# MinieasySens-RFM_V03-Build001.net
KiCad netlist of a schematic drawn in EAGLE
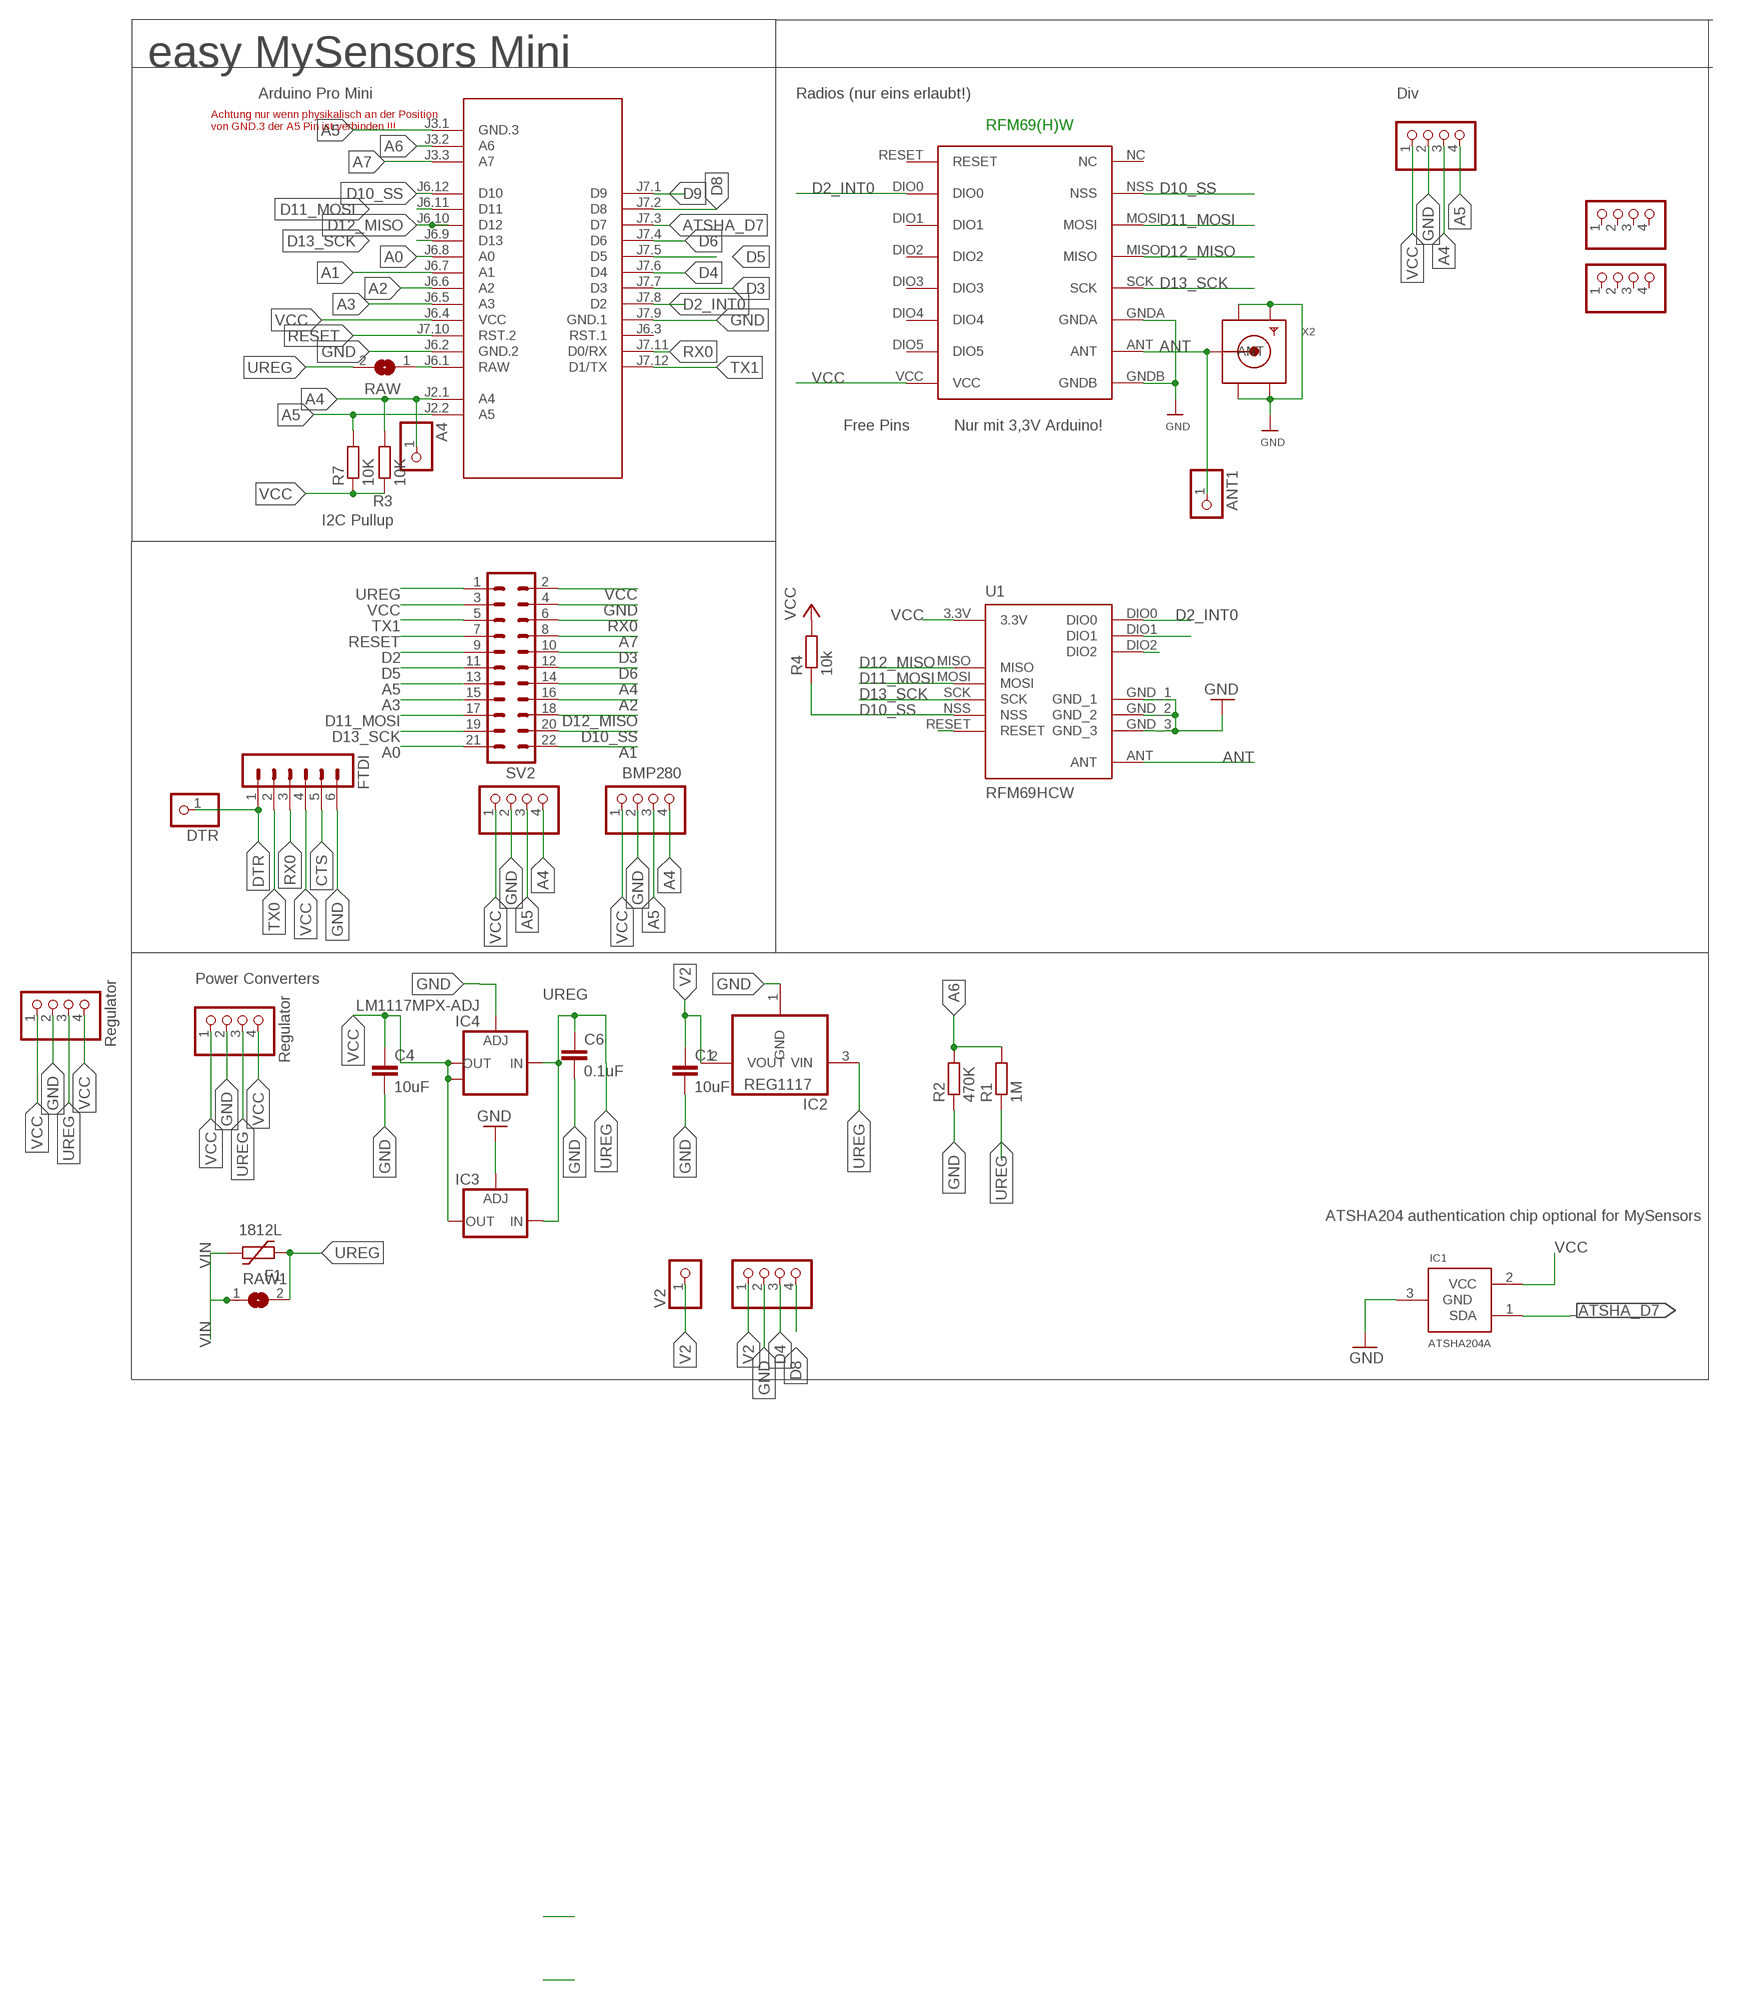
[diagram p0: schematic, sheet 1, part 1 of 2]
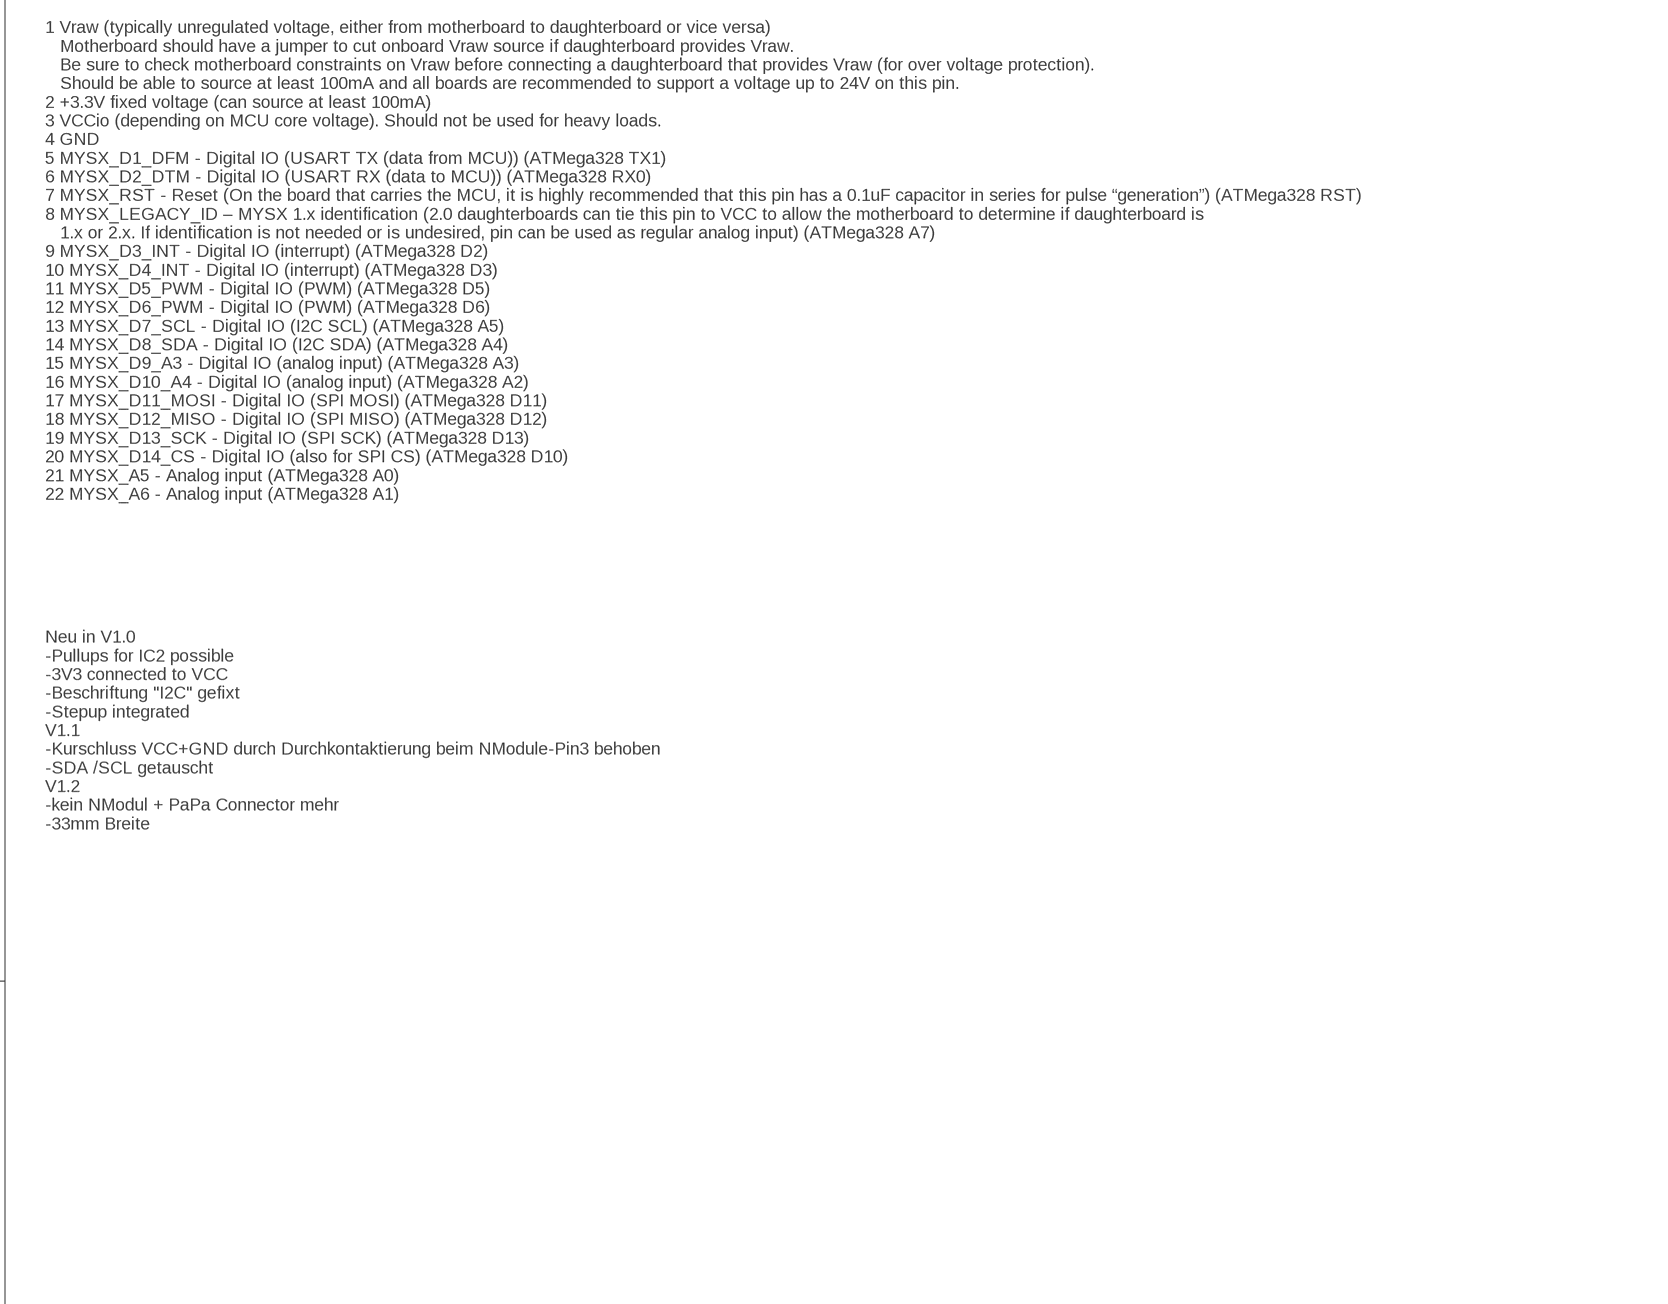
[diagram p1: schematic, sheet 1, part 2 of 2]

(export (version "E")
  (design (tool "Eeschema 10.0.6"))
  (components
    (comp (ref "A4")
      (value "PINHD-1X1")
      (footprint "eagle-import:1X01")
      (libsource (lib "eagle-import") (part "PINHD-1X1"))
    )
    (comp (ref "ANT1")
      (value "PINHD-1X1")
      (footprint "eagle-import:1X01")
      (libsource (lib "eagle-import") (part "PINHD-1X1"))
    )
    (comp (ref "BH1750")
      (value "PINHD-1X04_2.54-S")
      (footprint "eagle-import:1X04-S")
      (libsource (lib "eagle-import") (part "PINHD-1X04_2.54-S"))
    )
    (comp (ref "C1")
      (value "10uF")
      (footprint "eagle-import:C1210")
      (libsource (lib "eagle-import") (part "C-EUC1210"))
    )
    (comp (ref "C4")
      (value "10uF")
      (footprint "eagle-import:C1210")
      (libsource (lib "eagle-import") (part "C-EUC1210"))
    )
    (comp (ref "C6")
      (value "0.1uF")
      (footprint "eagle-import:C1206")
      (libsource (lib "eagle-import") (part "C-EUC1206"))
    )
    (comp (ref "DTR")
      (value "PINHD-1X1")
      (footprint "eagle-import:1X01")
      (libsource (lib "eagle-import") (part "PINHD-1X1"))
    )
    (comp (ref "F1")
      (value "1812L")
      (footprint "eagle-import:1812L")
      (libsource (lib "eagle-import") (part "1812L"))
    )
    (comp (ref "FTDI")
      (value "MA06-1")
      (footprint "eagle-import:MA06-1")
      (libsource (lib "eagle-import") (part "MA06-1"))
    )
    (comp (ref "I2C-1")
      (value "PINHD-1X04_2.54-S")
      (footprint "eagle-import:1X04-S")
      (libsource (lib "eagle-import") (part "PINHD-1X04_2.54-S"))
    )
    (comp (ref "I2C-2")
      (value "PINHD-1X04_2.54-S")
      (footprint "eagle-import:1X04-S")
      (libsource (lib "eagle-import") (part "PINHD-1X04_2.54-S"))
    )
    (comp (ref "IC1")
      (value "ATSHA204A")
      (footprint "eagle-import:SOT23")
      (libsource (lib "eagle-import") (part "ATSHA204A"))
    )
    (comp (ref "IC2")
      (value "REG1117")
      (footprint "eagle-import:SOT223")
      (libsource (lib "eagle-import") (part "REG1117"))
    )
    (comp (ref "IC3")
      (value "LD117ADT50TR")
      (footprint "eagle-import:DPACK")
      (libsource (lib "eagle-import") (part "LD117A?DT50TR"))
    )
    (comp (ref "IC4")
      (value "LM1117MPX-ADJ")
      (footprint "eagle-import:SOT223")
      (libsource (lib "eagle-import") (part "LM1117MPX-ADJ"))
    )
    (comp (ref "JP1")
      (value "PINHD-1X04_2.54-S")
      (footprint "eagle-import:1X04-S")
      (libsource (lib "eagle-import") (part "PINHD-1X04_2.54-S"))
    )
    (comp (ref "JP2")
      (value "PINHD-1X04_2.54-S")
      (footprint "eagle-import:1X04-S")
      (libsource (lib "eagle-import") (part "PINHD-1X04_2.54-S"))
    )
    (comp (ref "M1")
      (value "ARDUINO-PRO-MINI-3.3V#NP")
      (footprint "eagle-import:ARDUINO-PRO-MINI#NP")
      (libsource (lib "eagle-import") (part "ARDUINO-PRO-MINI-#NP3.3V"))
    )
    (comp (ref "R1")
      (value "1M")
      (footprint "eagle-import:R0805")
      (libsource (lib "eagle-import") (part "R-EU_R0805"))
    )
    (comp (ref "R2")
      (value "470K")
      (footprint "eagle-import:R0805")
      (libsource (lib "eagle-import") (part "R-EU_R0805"))
    )
    (comp (ref "R3")
      (value "10K")
      (footprint "eagle-import:R0805")
      (libsource (lib "eagle-import") (part "R-EU_R0805"))
    )
    (comp (ref "R4")
      (value "10k")
      (footprint "eagle-import:M0805")
      (libsource (lib "eagle-import") (part "R-EU_M0805"))
    )
    (comp (ref "R7")
      (value "10K")
      (footprint "eagle-import:R0805")
      (libsource (lib "eagle-import") (part "R-EU_R0805"))
    )
    (comp (ref "RAW") (value "SJ") (footprint "eagle-import:SJ") (libsource (lib "eagle-import") (part "SJ")))
    (comp (ref "RAW1")
      (value "SJ")
      (footprint "eagle-import:SJ")
      (libsource (lib "eagle-import") (part "SJ"))
    )
    (comp (ref "RFM69W")
      (value "RFM69HW")
      (footprint "eagle-import:RFM")
      (libsource (lib "eagle-import") (part "RFM69HW"))
    )
    (comp (ref "STEPDWN")
      (value "PINHD-1X04_2.54-S")
      (footprint "eagle-import:1X04-S")
      (libsource (lib "eagle-import") (part "PINHD-1X04_2.54-S"))
    )
    (comp (ref "STEPDWN1")
      (value "PINHD-1X04_2.54-S")
      (footprint "eagle-import:1X04-S")
      (libsource (lib "eagle-import") (part "PINHD-1X04_2.54-S"))
    )
    (comp (ref "SV2")
      (value "MA11-2")
      (footprint "eagle-import:MA11-2")
      (libsource (lib "eagle-import") (part "MA11-2"))
    )
    (comp (ref "U1")
      (value "RFM69HCW")
      (footprint "eagle-import:RFM69HCW-XXXS2")
      (libsource (lib "eagle-import") (part "RFM69HCW"))
    )
    (comp (ref "V2")
      (value "PINHD-1X1")
      (footprint "eagle-import:1X01")
      (libsource (lib "eagle-import") (part "PINHD-1X1"))
    )
    (comp (ref "V2-")
      (value "PINHD-1X04_2.54-S")
      (footprint "eagle-import:1X04-S")
      (libsource (lib "eagle-import") (part "PINHD-1X04_2.54-S"))
    )
    (comp (ref "X2")
      (value "SMACONNECTOR_EDGE")
      (footprint "eagle-import:SMA_EDGELAUNCH")
      (libsource (lib "eagle-import") (part "SMACONNECTOR_EDGE"))
    )
  )
  (nets
    (net (code "1") (name "/ANT") (class "Default")
      (node (ref "ANT1") (pin "1") (pinfunction "1_1") (pintype "passive"))
      (node (ref "RFM69W") (pin "ANT") (pinfunction "ANT_ANT") (pintype "bidirectional"))
      (node (ref "U1") (pin "ANT") (pinfunction "ANT_ANT") (pintype "passive"))
      (node (ref "X2") (pin "P") (pinfunction "ANT_P") (pintype "bidirectional"))
    )
    (net (code "2") (name "/D2") (class "Default")
      (node (ref "SV2") (pin "9") (pinfunction "9_9") (pintype "passive"))
    )
    (net (code "3") (name "/VIN") (class "Default")
      (node (ref "F1") (pin "P$2") (pinfunction "2_P$2") (pintype "passive"))
      (node (ref "RAW1") (pin "1") (pinfunction "1_1") (pintype "passive"))
    )
    (net (code "4") (name "A0") (class "Default")
      (node (ref "M1") (pin "J6.8") (pinfunction "A0_J6.8") (pintype "bidirectional"))
      (node (ref "SV2") (pin "21") (pinfunction "21_21") (pintype "passive"))
    )
    (net (code "5") (name "A1") (class "Default")
      (node (ref "M1") (pin "J6.7") (pinfunction "A1_J6.7") (pintype "bidirectional"))
      (node (ref "SV2") (pin "22") (pinfunction "22_22") (pintype "passive"))
    )
    (net (code "6") (name "A2") (class "Default")
      (node (ref "M1") (pin "J6.6") (pinfunction "A2_J6.6") (pintype "bidirectional"))
      (node (ref "SV2") (pin "16") (pinfunction "16_16") (pintype "passive"))
    )
    (net (code "7") (name "A3") (class "Default")
      (node (ref "M1") (pin "J6.5") (pinfunction "A3_J6.5") (pintype "bidirectional"))
      (node (ref "SV2") (pin "15") (pinfunction "15_15") (pintype "passive"))
    )
    (net (code "8") (name "A4") (class "Default")
      (node (ref "A4") (pin "1") (pinfunction "1_1") (pintype "passive"))
      (node (ref "BH1750") (pin "4") (pinfunction "4_4") (pintype "passive"))
      (node (ref "I2C-1") (pin "4") (pinfunction "4_4") (pintype "passive"))
      (node (ref "I2C-2") (pin "3") (pinfunction "3_3") (pintype "passive"))
      (node (ref "M1") (pin "J2.1") (pinfunction "A4_J2.1") (pintype "bidirectional"))
      (node (ref "R3") (pin "2") (pinfunction "2_2") (pintype "passive"))
      (node (ref "SV2") (pin "14") (pinfunction "14_14") (pintype "passive"))
    )
    (net (code "9") (name "A5") (class "Default")
      (node (ref "BH1750") (pin "3") (pinfunction "3_3") (pintype "passive"))
      (node (ref "I2C-1") (pin "3") (pinfunction "3_3") (pintype "passive"))
      (node (ref "I2C-2") (pin "4") (pinfunction "4_4") (pintype "passive"))
      (node (ref "M1") (pin "J2.2") (pinfunction "A5_J2.2") (pintype "bidirectional"))
      (node (ref "M1") (pin "J3.1") (pinfunction "GND.3_J3.1") (pintype "bidirectional"))
      (node (ref "R7") (pin "2") (pinfunction "2_2") (pintype "passive"))
      (node (ref "SV2") (pin "13") (pinfunction "13_13") (pintype "passive"))
    )
    (net (code "10") (name "A6") (class "Default")
      (node (ref "M1") (pin "J3.2") (pinfunction "A6_J3.2") (pintype "bidirectional"))
      (node (ref "R1") (pin "2") (pinfunction "2_2") (pintype "passive"))
      (node (ref "R2") (pin "2") (pinfunction "2_2") (pintype "passive"))
    )
    (net (code "11") (name "A7") (class "Default")
      (node (ref "M1") (pin "J3.3") (pinfunction "A7_J3.3") (pintype "bidirectional"))
      (node (ref "SV2") (pin "8") (pinfunction "8_8") (pintype "passive"))
    )
    (net (code "12") (name "ATSHA_D7") (class "Default")
      (node (ref "IC1") (pin "1") (pinfunction "SDA_1") (pintype "bidirectional"))
      (node (ref "M1") (pin "J7.3") (pinfunction "D7_J7.3") (pintype "bidirectional"))
    )
    (net (code "13") (name "CTS") (class "Default")
      (node (ref "FTDI") (pin "5") (pinfunction "5_5") (pintype "passive"))
    )
    (net (code "14") (name "D2_INT0") (class "Default")
      (node (ref "M1") (pin "J7.8") (pinfunction "D2_J7.8") (pintype "bidirectional"))
      (node (ref "RFM69W") (pin "DIO0") (pinfunction "DIO0_DIO0") (pintype "bidirectional"))
      (node (ref "U1") (pin "DIO0") (pinfunction "DIO0_DIO0") (pintype "bidirectional"))
    )
    (net (code "15") (name "D3") (class "Default")
      (node (ref "M1") (pin "J7.7") (pinfunction "D3_J7.7") (pintype "bidirectional"))
      (node (ref "SV2") (pin "10") (pinfunction "10_10") (pintype "passive"))
    )
    (net (code "16") (name "D4") (class "Default")
      (node (ref "M1") (pin "J7.6") (pinfunction "D4_J7.6") (pintype "bidirectional"))
      (node (ref "V2-") (pin "3") (pinfunction "3_3") (pintype "passive"))
    )
    (net (code "17") (name "D5") (class "Default")
      (node (ref "M1") (pin "J7.5") (pinfunction "D5_J7.5") (pintype "bidirectional"))
      (node (ref "SV2") (pin "11") (pinfunction "11_11") (pintype "passive"))
    )
    (net (code "18") (name "D6") (class "Default")
      (node (ref "M1") (pin "J7.4") (pinfunction "D6_J7.4") (pintype "bidirectional"))
      (node (ref "SV2") (pin "12") (pinfunction "12_12") (pintype "passive"))
    )
    (net (code "19") (name "D8") (class "Default")
      (node (ref "M1") (pin "J7.2") (pinfunction "D8_J7.2") (pintype "bidirectional"))
      (node (ref "V2-") (pin "4") (pinfunction "4_4") (pintype "passive"))
    )
    (net (code "20") (name "D9") (class "Default")
      (node (ref "M1") (pin "J7.1") (pinfunction "D9_J7.1") (pintype "bidirectional"))
    )
    (net (code "21") (name "D10_SS") (class "Default")
      (node (ref "M1") (pin "J6.12") (pinfunction "D10_J6.12") (pintype "bidirectional"))
      (node (ref "R4") (pin "1") (pinfunction "1_1") (pintype "passive"))
      (node (ref "RFM69W") (pin "NSS") (pinfunction "NSS_NSS") (pintype "bidirectional"))
      (node (ref "SV2") (pin "20") (pinfunction "20_20") (pintype "passive"))
      (node (ref "U1") (pin "NSS") (pinfunction "NSS_NSS") (pintype "input"))
    )
    (net (code "22") (name "D11_MOSI") (class "Default")
      (node (ref "M1") (pin "J6.11") (pinfunction "D11_J6.11") (pintype "bidirectional"))
      (node (ref "RFM69W") (pin "MOSI") (pinfunction "MOSI_MOSI") (pintype "bidirectional"))
      (node (ref "SV2") (pin "17") (pinfunction "17_17") (pintype "passive"))
      (node (ref "U1") (pin "MOSI") (pinfunction "MOSI_MOSI") (pintype "input"))
    )
    (net (code "23") (name "D12_MISO") (class "Default")
      (node (ref "M1") (pin "J6.10") (pinfunction "D12_J6.10") (pintype "bidirectional"))
      (node (ref "RFM69W") (pin "MISO") (pinfunction "MISO_MISO") (pintype "bidirectional"))
      (node (ref "SV2") (pin "18") (pinfunction "18_18") (pintype "passive"))
      (node (ref "U1") (pin "MISO") (pinfunction "MISO_MISO") (pintype "bidirectional"))
    )
    (net (code "24") (name "D13_SCK") (class "Default")
      (node (ref "M1") (pin "J6.9") (pinfunction "D13_J6.9") (pintype "bidirectional"))
      (node (ref "RFM69W") (pin "SCK") (pinfunction "SCK_SCK") (pintype "bidirectional"))
      (node (ref "SV2") (pin "19") (pinfunction "19_19") (pintype "passive"))
      (node (ref "U1") (pin "SCK") (pinfunction "SCK_SCK") (pintype "input"))
    )
    (net (code "25") (name "DTR") (class "Default")
      (node (ref "DTR") (pin "1") (pinfunction "1_1") (pintype "passive"))
      (node (ref "FTDI") (pin "1") (pinfunction "1_1") (pintype "passive"))
    )
    (net (code "26") (name "GND") (class "Default")
      (node (ref "BH1750") (pin "2") (pinfunction "2_2") (pintype "passive"))
      (node (ref "C1") (pin "2") (pinfunction "2_2") (pintype "passive"))
      (node (ref "C4") (pin "2") (pinfunction "2_2") (pintype "passive"))
      (node (ref "C6") (pin "2") (pinfunction "2_2") (pintype "passive"))
      (node (ref "FTDI") (pin "6") (pinfunction "6_6") (pintype "passive"))
      (node (ref "I2C-1") (pin "2") (pinfunction "2_2") (pintype "passive"))
      (node (ref "I2C-2") (pin "2") (pinfunction "2_2") (pintype "passive"))
      (node (ref "IC1") (pin "3") (pinfunction "GND_3") (pintype "bidirectional"))
      (node (ref "IC2") (pin "1") (pinfunction "GND_1") (pintype "power_in"))
      (node (ref "IC3") (pin "1") (pinfunction "ADJ_1") (pintype "input"))
      (node (ref "IC4") (pin "1") (pinfunction "ADJ_1") (pintype "input"))
      (node (ref "M1") (pin "J6.2") (pinfunction "GND.2_J6.2") (pintype "power_in"))
      (node (ref "M1") (pin "J7.9") (pinfunction "GND.1_J7.9") (pintype "power_in"))
      (node (ref "R2") (pin "1") (pinfunction "1_1") (pintype "passive"))
      (node (ref "RFM69W") (pin "GNDA") (pinfunction "GNDA_GNDA") (pintype "bidirectional"))
      (node (ref "RFM69W") (pin "GNDB") (pinfunction "GNDB_GNDB") (pintype "bidirectional"))
      (node (ref "STEPDWN") (pin "2") (pinfunction "2_2") (pintype "passive"))
      (node (ref "STEPDWN1") (pin "2") (pinfunction "2_2") (pintype "passive"))
      (node (ref "SV2") (pin "4") (pinfunction "4_4") (pintype "passive"))
      (node (ref "U1") (pin "GND_1") (pinfunction "GND_1_GND_1") (pintype "power_in"))
      (node (ref "U1") (pin "GND_2") (pinfunction "GND_2_GND_2") (pintype "power_in"))
      (node (ref "U1") (pin "GND_3") (pinfunction "GND_3_GND_3") (pintype "power_in"))
      (node (ref "V2-") (pin "2") (pinfunction "2_2") (pintype "passive"))
      (node (ref "X2") (pin "GND@1") (pinfunction "GND4_GND@1") (pintype "power_in"))
      (node (ref "X2") (pin "GND@2") (pinfunction "GND3_GND@2") (pintype "power_in"))
      (node (ref "X2") (pin "GND@3") (pinfunction "GND2_GND@3") (pintype "power_in"))
      (node (ref "X2") (pin "GND@4") (pinfunction "GND1_GND@4") (pintype "power_in"))
    )
    (net (code "27") (name "Net-(M1-RAW)") (class "Default")
      (node (ref "M1") (pin "J6.1") (pinfunction "RAW_J6.1") (pintype "power_in"))
      (node (ref "RAW") (pin "1") (pinfunction "1_1") (pintype "passive"))
    )
    (net (code "28") (name "RESET") (class "Default")
      (node (ref "M1") (pin "J7.10") (pinfunction "RST.2_J7.10") (pintype "bidirectional"))
      (node (ref "SV2") (pin "7") (pinfunction "7_7") (pintype "passive"))
    )
    (net (code "29") (name "RX0") (class "Default")
      (node (ref "FTDI") (pin "3") (pinfunction "3_3") (pintype "passive"))
      (node (ref "M1") (pin "J7.11") (pinfunction "D0/RX_J7.11") (pintype "bidirectional"))
      (node (ref "SV2") (pin "6") (pinfunction "6_6") (pintype "passive"))
    )
    (net (code "30") (name "TX0") (class "Default")
      (node (ref "FTDI") (pin "2") (pinfunction "2_2") (pintype "passive"))
    )
    (net (code "31") (name "TX1") (class "Default")
      (node (ref "M1") (pin "J7.12") (pinfunction "D1/TX_J7.12") (pintype "bidirectional"))
      (node (ref "SV2") (pin "5") (pinfunction "5_5") (pintype "passive"))
    )
    (net (code "32") (name "UREG") (class "Default")
      (node (ref "C6") (pin "1") (pinfunction "1_1") (pintype "passive"))
      (node (ref "F1") (pin "P$1") (pinfunction "1_P$1") (pintype "passive"))
      (node (ref "IC2") (pin "3") (pinfunction "VIN_3") (pintype "input"))
      (node (ref "IC3") (pin "3") (pinfunction "IN_3") (pintype "input"))
      (node (ref "IC4") (pin "3") (pinfunction "IN_3") (pintype "input"))
      (node (ref "R1") (pin "1") (pinfunction "1_1") (pintype "passive"))
      (node (ref "RAW") (pin "2") (pinfunction "2_2") (pintype "passive"))
      (node (ref "RAW1") (pin "2") (pinfunction "2_2") (pintype "passive"))
      (node (ref "STEPDWN") (pin "3") (pinfunction "3_3") (pintype "passive"))
      (node (ref "STEPDWN1") (pin "3") (pinfunction "3_3") (pintype "passive"))
      (node (ref "SV2") (pin "1") (pinfunction "1_1") (pintype "passive"))
    )
    (net (code "33") (name "V2") (class "Default")
      (node (ref "C1") (pin "1") (pinfunction "1_1") (pintype "passive"))
      (node (ref "IC2") (pin "2") (pinfunction "VOUT_2") (pintype "output"))
      (node (ref "V2") (pin "1") (pinfunction "1_1") (pintype "passive"))
      (node (ref "V2-") (pin "1") (pinfunction "1_1") (pintype "passive"))
    )
    (net (code "34") (name "VCC") (class "Default")
      (node (ref "BH1750") (pin "1") (pinfunction "1_1") (pintype "passive"))
      (node (ref "C4") (pin "1") (pinfunction "1_1") (pintype "passive"))
      (node (ref "FTDI") (pin "4") (pinfunction "4_4") (pintype "passive"))
      (node (ref "I2C-1") (pin "1") (pinfunction "1_1") (pintype "passive"))
      (node (ref "I2C-2") (pin "1") (pinfunction "1_1") (pintype "passive"))
      (node (ref "IC1") (pin "2") (pinfunction "VCC_2") (pintype "bidirectional"))
      (node (ref "IC3") (pin "4") (pinfunction "OUT_4") (pintype "passive"))
      (node (ref "IC4") (pin "2") (pinfunction "OUT_2") (pintype "passive"))
      (node (ref "IC4") (pin "TAB") (pinfunction "OUT1_TAB") (pintype "passive"))
      (node (ref "M1") (pin "J6.4") (pinfunction "VCC_J6.4") (pintype "power_in"))
      (node (ref "R3") (pin "1") (pinfunction "1_1") (pintype "passive"))
      (node (ref "R4") (pin "2") (pinfunction "2_2") (pintype "passive"))
      (node (ref "R7") (pin "1") (pinfunction "1_1") (pintype "passive"))
      (node (ref "RFM69W") (pin "VCC") (pinfunction "VCC_VCC") (pintype "bidirectional"))
      (node (ref "STEPDWN") (pin "1") (pinfunction "1_1") (pintype "passive"))
      (node (ref "STEPDWN") (pin "4") (pinfunction "4_4") (pintype "passive"))
      (node (ref "STEPDWN1") (pin "1") (pinfunction "1_1") (pintype "passive"))
      (node (ref "STEPDWN1") (pin "4") (pinfunction "4_4") (pintype "passive"))
      (node (ref "SV2") (pin "2") (pinfunction "2_2") (pintype "passive"))
      (node (ref "SV2") (pin "3") (pinfunction "3_3") (pintype "passive"))
      (node (ref "U1") (pin "3.3V") (pinfunction "3.3V_3.3V") (pintype "power_in"))
    )
    (net (code "35") (name "unconnected-(JP1-Pad1)") (class "Default")
      (node (ref "JP1") (pin "1") (pinfunction "1_1") (pintype "passive"))
    )
    (net (code "36") (name "unconnected-(JP1-Pad2)") (class "Default")
      (node (ref "JP1") (pin "2") (pinfunction "2_2") (pintype "passive"))
    )
    (net (code "37") (name "unconnected-(JP1-Pad3)") (class "Default")
      (node (ref "JP1") (pin "3") (pinfunction "3_3") (pintype "passive"))
    )
    (net (code "38") (name "unconnected-(JP1-Pad4)") (class "Default")
      (node (ref "JP1") (pin "4") (pinfunction "4_4") (pintype "passive"))
    )
    (net (code "39") (name "unconnected-(JP2-Pad1)") (class "Default")
      (node (ref "JP2") (pin "1") (pinfunction "1_1") (pintype "passive"))
    )
    (net (code "40") (name "unconnected-(JP2-Pad2)") (class "Default")
      (node (ref "JP2") (pin "2") (pinfunction "2_2") (pintype "passive"))
    )
    (net (code "41") (name "unconnected-(JP2-Pad3)") (class "Default")
      (node (ref "JP2") (pin "3") (pinfunction "3_3") (pintype "passive"))
    )
    (net (code "42") (name "unconnected-(JP2-Pad4)") (class "Default")
      (node (ref "JP2") (pin "4") (pinfunction "4_4") (pintype "passive"))
    )
    (net (code "43") (name "unconnected-(M1-RST.1-PadJ6.3)") (class "Default")
      (node (ref "M1") (pin "J6.3") (pinfunction "RST.1_J6.3") (pintype "bidirectional"))
    )
    (net (code "44") (name "unconnected-(RFM69W-PadDIO1)") (class "Default")
      (node (ref "RFM69W") (pin "DIO1") (pinfunction "DIO1_DIO1") (pintype "bidirectional"))
    )
    (net (code "45") (name "unconnected-(RFM69W-PadDIO2)") (class "Default")
      (node (ref "RFM69W") (pin "DIO2") (pinfunction "DIO2_DIO2") (pintype "bidirectional"))
    )
    (net (code "46") (name "unconnected-(RFM69W-PadDIO3)") (class "Default")
      (node (ref "RFM69W") (pin "DIO3") (pinfunction "DIO3_DIO3") (pintype "bidirectional"))
    )
    (net (code "47") (name "unconnected-(RFM69W-PadDIO4)") (class "Default")
      (node (ref "RFM69W") (pin "DIO4") (pinfunction "DIO4_DIO4") (pintype "bidirectional"))
    )
    (net (code "48") (name "unconnected-(RFM69W-PadDIO5)") (class "Default")
      (node (ref "RFM69W") (pin "DIO5") (pinfunction "DIO5_DIO5") (pintype "bidirectional"))
    )
    (net (code "49") (name "unconnected-(RFM69W-PadNC)") (class "Default")
      (node (ref "RFM69W") (pin "NC") (pinfunction "NC_NC") (pintype "bidirectional"))
    )
    (net (code "50") (name "unconnected-(RFM69W-PadRESET)") (class "Default")
      (node (ref "RFM69W") (pin "RESET") (pinfunction "RESET_RESET") (pintype "bidirectional"))
    )
    (net (code "51") (name "unconnected-(U1-PadDIO1)") (class "Default")
      (node (ref "U1") (pin "DIO1") (pinfunction "DIO1_DIO1") (pintype "bidirectional"))
    )
    (net (code "52") (name "unconnected-(U1-PadDIO2)") (class "Default")
      (node (ref "U1") (pin "DIO2") (pinfunction "DIO2_DIO2") (pintype "bidirectional"))
    )
    (net (code "53") (name "unconnected-(U1-PadRESET)") (class "Default")
      (node (ref "U1") (pin "RESET") (pinfunction "RESET_RESET") (pintype "input"))
    )
  )
)
